# SCH_Imposter-Game_2026-03-29.net
KiCad netlist of a schematic drawn in EasyEDA
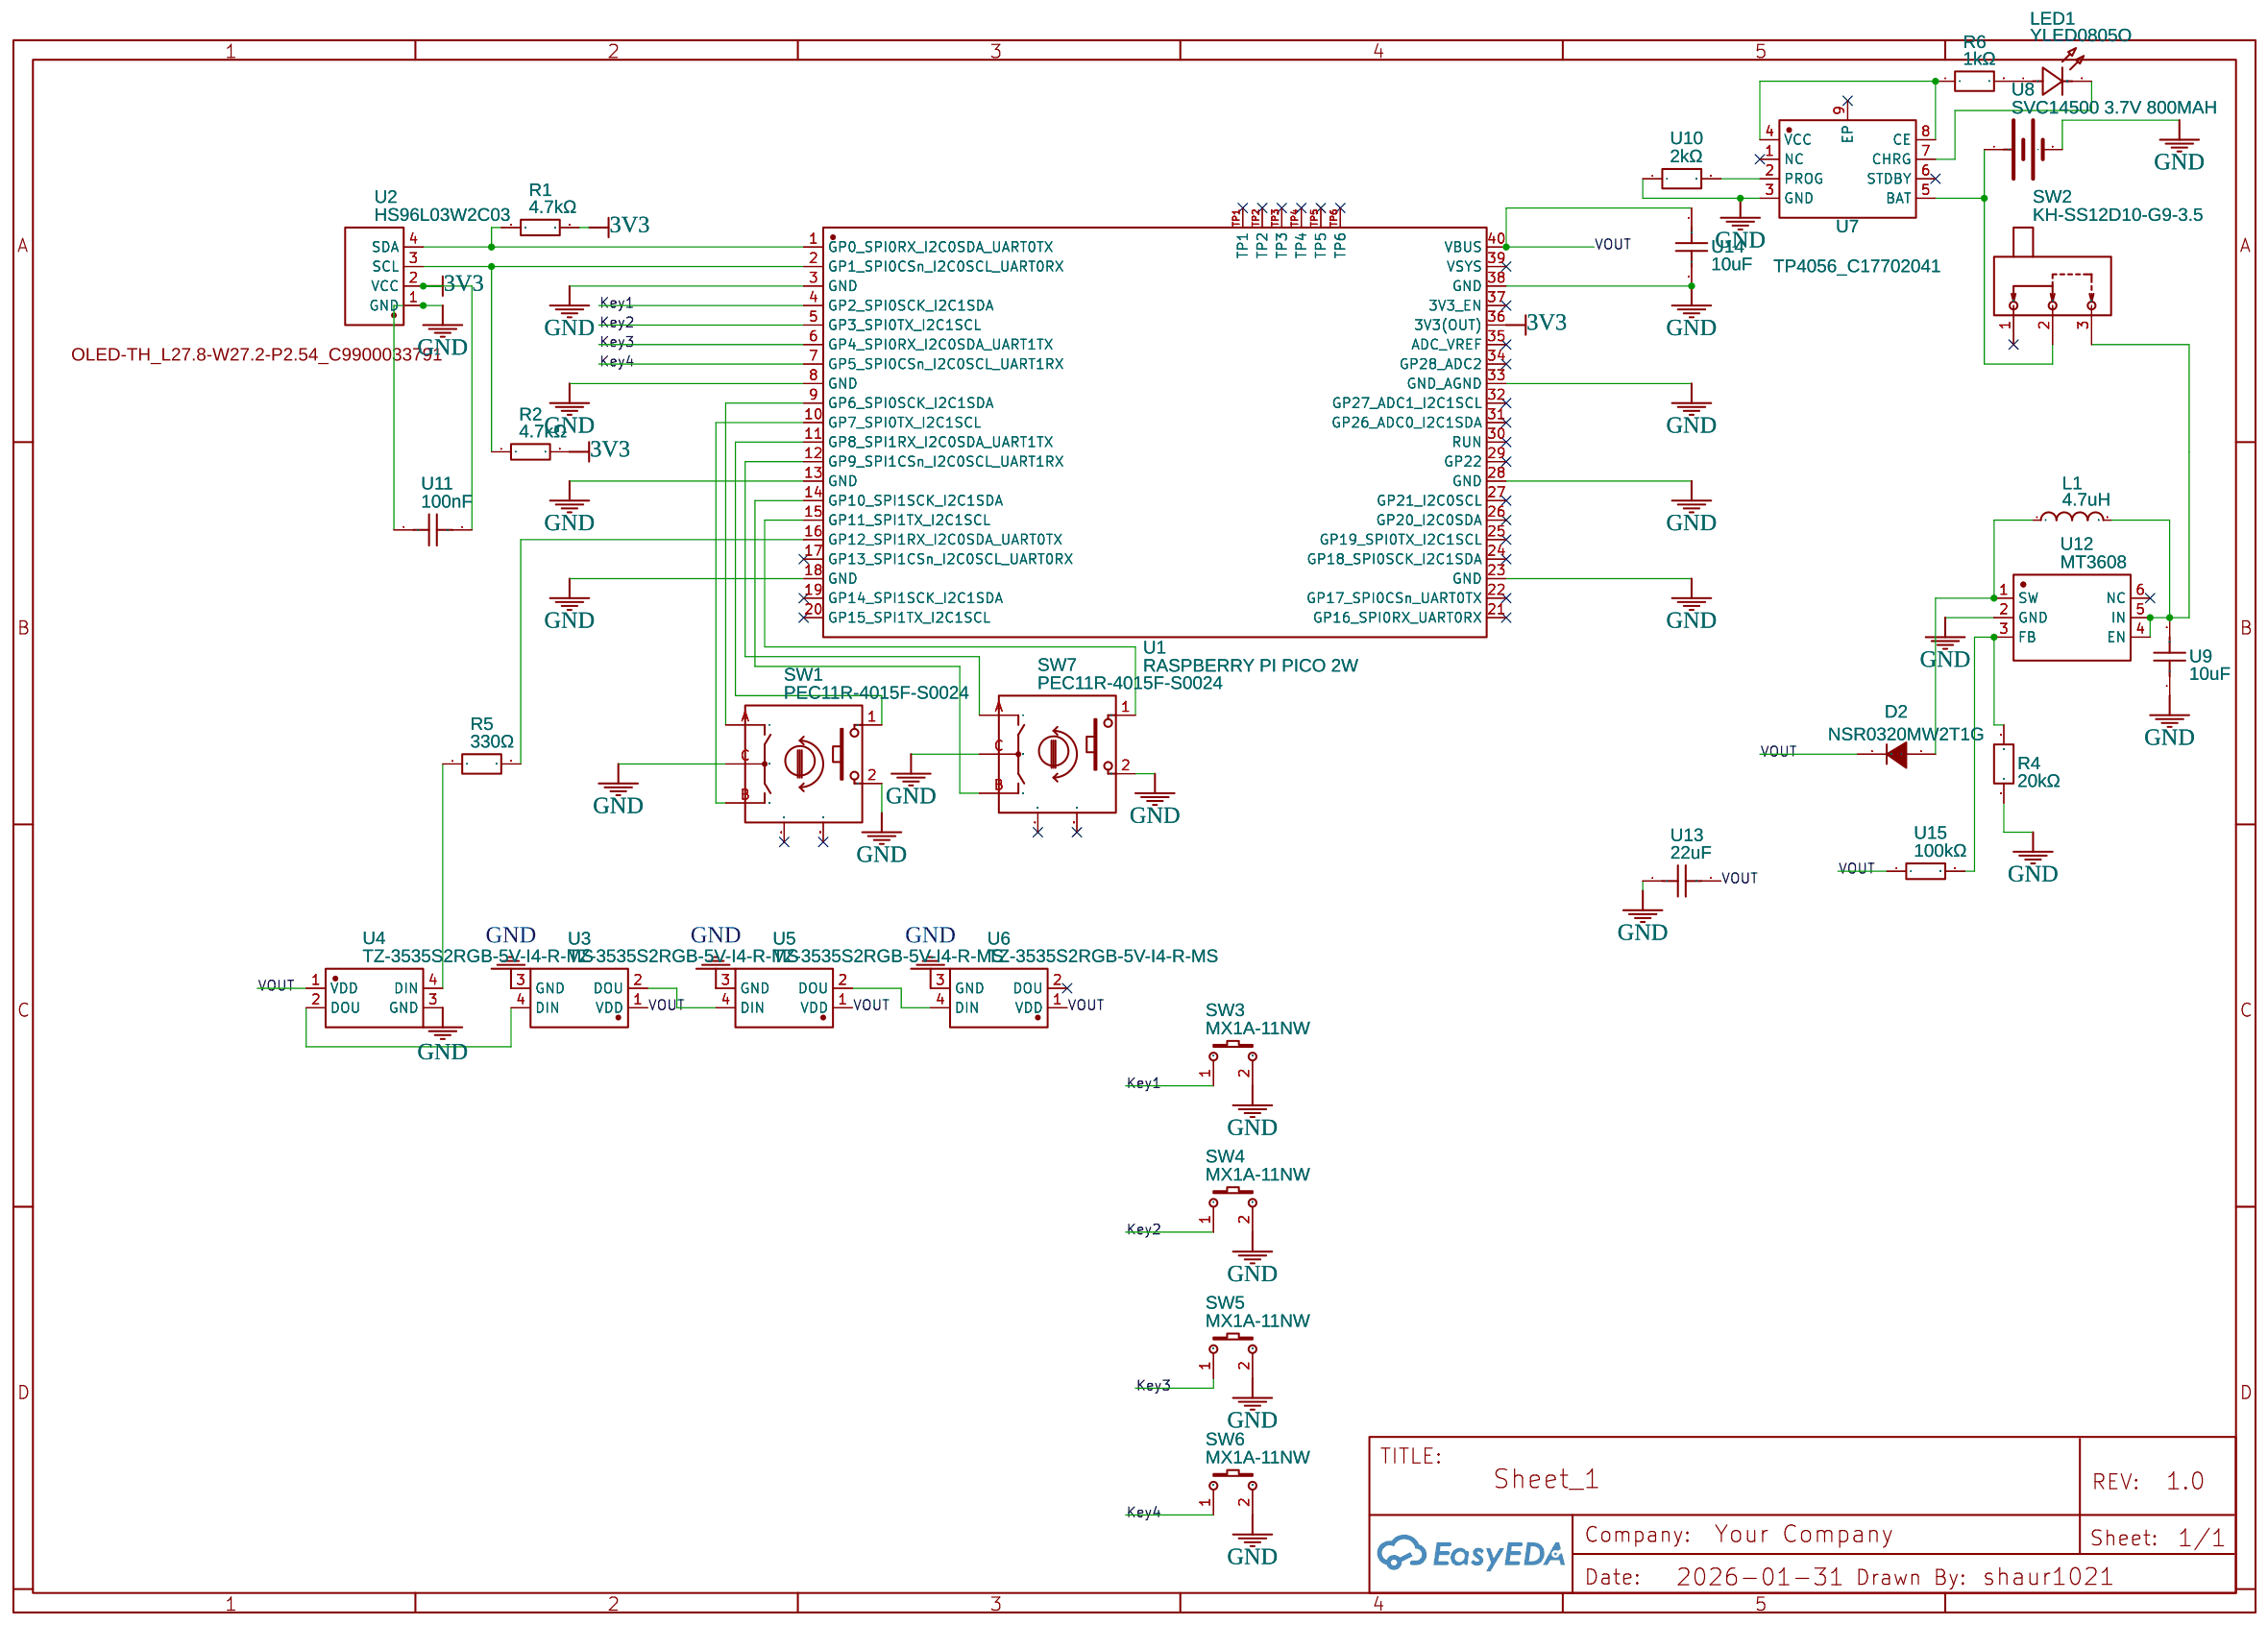
[diagram p0: schematic sheet]

(export (version "E")
  (design (tool "Eeschema 10.0.6"))
  (components
    (comp (ref "D2")
      (value "NSR0320MW2T1G")
      (fields (field (name "Manufacturer") "onsemi(安森美)"))
      (libsource (lib "") (part "NSR0320MW2T1G"))
    )
    (comp (ref "L1")
      (value "4.7uH")
      (fields (field (name "Manufacturer Part") "CD32N-4R7M") (field (name "Manufacturer") "MINGSTAR(登壹)"))
      (libsource (lib "") (part "CD32N-4R7M"))
    )
    (comp (ref "LED1")
      (value "YLED0805O")
      (fields (field (name "Manufacturer") "YONGYUTAI(永裕泰)"))
      (libsource (lib "") (part "YLED0805O"))
    )
    (comp (ref "R1")
      (value "4.7kΩ")
      (fields (field (name "Manufacturer Part") "CR254701F") (field (name "Manufacturer") "Meritek"))
      (libsource (lib "") (part "CR254701F"))
    )
    (comp (ref "R2")
      (value "4.7kΩ")
      (fields (field (name "Manufacturer Part") "CR254701F") (field (name "Manufacturer") "Meritek"))
      (libsource (lib "") (part "CR254701F"))
    )
    (comp (ref "R4")
      (value "20kΩ")
      (fields (field (name "Manufacturer Part") "FRC1206F2002TS") (field (name "Manufacturer") "FOJAN(富捷)"))
      (libsource (lib "") (part "FRC1206F2002TS"))
    )
    (comp (ref "R5")
      (value "330Ω")
      (fields
        (field (name "Manufacturer Part") "CRCW0805330RJNEA")
        (field (name "Manufacturer") "VISHAY(威世)")
      )
      (libsource (lib "") (part "CRCW0805330RJNEA"))
    )
    (comp (ref "R6")
      (value "1kΩ")
      (fields (field (name "Manufacturer Part") "APC0603B1K00N") (field (name "Manufacturer") "Ohmite"))
      (libsource (lib "") (part "APC0603B1K00N"))
    )
    (comp (ref "SW1")
      (value "PEC11R-4015F-S0024")
      (fields (field (name "Manufacturer") "BOURNS"))
      (libsource (lib "") (part "PEC11R-4015F-S0024"))
    )
    (comp (ref "SW2")
      (value "KH-SS12D10-G9-3.5")
      (fields (field (name "Manufacturer") "kinghelm(金航标)"))
      (libsource (lib "") (part "KH-SS12D10-G9-3.5"))
    )
    (comp (ref "SW3")
      (value "MX1A-11NW")
      (fields (field (name "Manufacturer") "CHERRY"))
      (libsource (lib "") (part "MX1A-11NW"))
    )
    (comp (ref "SW4")
      (value "MX1A-11NW")
      (fields (field (name "Manufacturer") "CHERRY"))
      (libsource (lib "") (part "MX1A-11NW"))
    )
    (comp (ref "SW5")
      (value "MX1A-11NW")
      (fields (field (name "Manufacturer") "CHERRY"))
      (libsource (lib "") (part "MX1A-11NW"))
    )
    (comp (ref "SW6")
      (value "MX1A-11NW")
      (fields (field (name "Manufacturer") "CHERRY"))
      (libsource (lib "") (part "MX1A-11NW"))
    )
    (comp (ref "SW7")
      (value "PEC11R-4015F-S0024")
      (fields (field (name "Manufacturer") "BOURNS"))
      (libsource (lib "") (part "PEC11R-4015F-S0024"))
    )
    (comp (ref "U1")
      (value "RASPBERRY PI PICO 2W")
      (fields
        (field (name "Manufacturer Part") "Raspberry Pi Pico 2W")
        (field (name "Manufacturer") "Raspberry Pi(树莓派)")
      )
      (libsource (lib "") (part "RASPBERRY PI PICO 2W"))
    )
    (comp (ref "U2")
      (value "HS96L03W2C03")
      (fields (field (name "Manufacturer") "HS(汉昇)"))
      (libsource (lib "") (part "HS96L03W2C03"))
    )
    (comp (ref "U3")
      (value "TZ-3535S2RGB-5V-I4-R-MS")
      (fields (field (name "Manufacturer") "TUOZHAN(拓展光电)"))
      (libsource (lib "") (part "TZ-3535S2RGB-5V-I4-R-MS_1"))
    )
    (comp (ref "U4")
      (value "TZ-3535S2RGB-5V-I4-R-MS")
      (fields (field (name "Manufacturer") "TUOZHAN(拓展光电)"))
      (libsource (lib "") (part "TZ-3535S2RGB-5V-I4-R-MS"))
    )
    (comp (ref "U5")
      (value "TZ-3535S2RGB-5V-I4-R-MS")
      (fields (field (name "Manufacturer") "TUOZHAN(拓展光电)"))
      (libsource (lib "") (part "TZ-3535S2RGB-5V-I4-R-MS_1"))
    )
    (comp (ref "U6")
      (value "TZ-3535S2RGB-5V-I4-R-MS")
      (fields (field (name "Manufacturer") "TUOZHAN(拓展光电)"))
      (libsource (lib "") (part "TZ-3535S2RGB-5V-I4-R-MS_1"))
    )
    (comp (ref "U7")
      (value "TP4056_C17702041")
      (fields (field (name "Manufacturer Part") "TP4056") (field (name "Manufacturer") "HXY MOSFET(华轩阳电子)"))
      (libsource (lib "") (part "TP4056_C17702041"))
    )
    (comp (ref "U8")
      (value "SVC14500 3.7V 800MAH")
      (fields
        (field (name "Manufacturer Part") "SVC14500 3.7V 800mAh")
        (field (name "Manufacturer") "Sharvin Power(经钛电子)")
      )
      (libsource (lib "") (part "SVC14500 3.7V 800MAH"))
    )
    (comp (ref "U9")
      (value "10uF")
      (fields (field (name "Manufacturer Part") "C4532X7R1C106M230KA") (field (name "Manufacturer") "TDK"))
      (libsource (lib "") (part "C4532X7R1C106M230KA_1"))
    )
    (comp (ref "U10")
      (value "2kΩ")
      (fields
        (field (name "Manufacturer Part") "TNPW04022K00BYEP")
        (field (name "Manufacturer") "VISHAY(威世)")
      )
      (libsource (lib "") (part "TNPW04022K00BYEP"))
    )
    (comp (ref "U11")
      (value "100nF")
      (fields (field (name "Manufacturer Part") "C1005X5R1A104K050BA") (field (name "Manufacturer") "TDK"))
      (libsource (lib "") (part "C1005X5R1A104K050BA"))
    )
    (comp (ref "U12")
      (value "MT3608")
      (fields (field (name "Manufacturer") "西安航天民芯"))
      (libsource (lib "") (part "MT3608"))
    )
    (comp (ref "U13")
      (value "22uF")
      (fields
        (field (name "Manufacturer Part") "MCAST32MSB7226KPNA01")
        (field (name "Manufacturer") "TAIYO YUDEN(太诱)")
      )
      (libsource (lib "") (part "MCAST32MSB7226KPNA01"))
    )
    (comp (ref "U14")
      (value "10uF")
      (fields (field (name "Manufacturer Part") "C4532X7R1C106M230KA") (field (name "Manufacturer") "TDK"))
      (libsource (lib "") (part "C4532X7R1C106M230KA"))
    )
    (comp (ref "U15")
      (value "100kΩ")
      (fields (field (name "Manufacturer Part") "CHR0805H-100KJ8") (field (name "Manufacturer") "Riedon"))
      (libsource (lib "") (part "CHR0805H-100KJ8"))
    )
  )
  (nets
    (net (code "1") (name "/Key1") (class "Default")
      (node (ref "SW3") (pin "1") (pinfunction "1_1") (pintype "unspecified"))
      (node (ref "U1") (pin "4") (pinfunction "GP2_SPI0SCK_I2C1SDA_4") (pintype "unspecified"))
    )
    (net (code "2") (name "/Key2") (class "Default")
      (node (ref "SW4") (pin "1") (pinfunction "1_1") (pintype "unspecified"))
      (node (ref "U1") (pin "5") (pinfunction "GP3_SPI0TX_I2C1SCL_5") (pintype "unspecified"))
    )
    (net (code "3") (name "/Key3") (class "Default")
      (node (ref "SW5") (pin "1") (pinfunction "1_1") (pintype "unspecified"))
      (node (ref "U1") (pin "6") (pinfunction "GP4_SPI0RX_I2C0SDA_UART1TX_6") (pintype "unspecified"))
    )
    (net (code "4") (name "/Key4") (class "Default")
      (node (ref "SW6") (pin "1") (pinfunction "1_1") (pintype "unspecified"))
      (node (ref "U1") (pin "7") (pinfunction "GP5_SPI0CSn_I2C0SCL_UART1RX_7") (pintype "unspecified"))
    )
    (net (code "5") (name "/VOUT") (class "Default")
      (node (ref "D2") (pin "1") (pinfunction "C_1") (pintype "unspecified"))
      (node (ref "U1") (pin "40") (pinfunction "VBUS_40") (pintype "unspecified"))
      (node (ref "U13") (pin "2") (pinfunction "2_2") (pintype "unspecified"))
      (node (ref "U14") (pin "1") (pinfunction "1_1") (pintype "unspecified"))
      (node (ref "U15") (pin "1") (pinfunction "1_1") (pintype "unspecified"))
      (node (ref "U3") (pin "1") (pinfunction "VDD_1") (pintype "unspecified"))
      (node (ref "U4") (pin "1") (pinfunction "VDD_1") (pintype "unspecified"))
      (node (ref "U5") (pin "1") (pinfunction "VDD_1") (pintype "unspecified"))
      (node (ref "U6") (pin "1") (pinfunction "VDD_1") (pintype "unspecified"))
    )
    (net (code "6") (name "3V3") (class "Default")
      (node (ref "R1") (pin "2") (pinfunction "2_2") (pintype "unspecified"))
      (node (ref "R2") (pin "2") (pinfunction "2_2") (pintype "unspecified"))
      (node (ref "U1") (pin "36") (pinfunction "3V3(OUT)_36") (pintype "unspecified"))
      (node (ref "U11") (pin "2") (pinfunction "2_2") (pintype "unspecified"))
      (node (ref "U2") (pin "2") (pinfunction "VCC_2") (pintype "unspecified"))
    )
    (net (code "7") (name "GND") (class "Default")
      (node (ref "R4") (pin "1") (pinfunction "1_1") (pintype "unspecified"))
      (node (ref "SW1") (pin "2") (pinfunction "2_2") (pintype "unspecified"))
      (node (ref "SW1") (pin "C") (pinfunction "C_C") (pintype "unspecified"))
      (node (ref "SW3") (pin "2") (pinfunction "2_2") (pintype "unspecified"))
      (node (ref "SW4") (pin "2") (pinfunction "2_2") (pintype "unspecified"))
      (node (ref "SW5") (pin "2") (pinfunction "2_2") (pintype "unspecified"))
      (node (ref "SW6") (pin "2") (pinfunction "2_2") (pintype "unspecified"))
      (node (ref "SW7") (pin "2") (pinfunction "2_2") (pintype "unspecified"))
      (node (ref "SW7") (pin "C") (pinfunction "C_C") (pintype "unspecified"))
      (node (ref "U1") (pin "13") (pinfunction "GND_13") (pintype "unspecified"))
      (node (ref "U1") (pin "18") (pinfunction "GND_18") (pintype "unspecified"))
      (node (ref "U1") (pin "23") (pinfunction "GND_23") (pintype "unspecified"))
      (node (ref "U1") (pin "28") (pinfunction "GND_28") (pintype "unspecified"))
      (node (ref "U1") (pin "3") (pinfunction "GND_3") (pintype "unspecified"))
      (node (ref "U1") (pin "33") (pinfunction "GND_AGND_33") (pintype "unspecified"))
      (node (ref "U1") (pin "38") (pinfunction "GND_38") (pintype "unspecified"))
      (node (ref "U1") (pin "8") (pinfunction "GND_8") (pintype "unspecified"))
      (node (ref "U10") (pin "1") (pinfunction "1_1") (pintype "unspecified"))
      (node (ref "U11") (pin "1") (pinfunction "1_1") (pintype "unspecified"))
      (node (ref "U12") (pin "2") (pinfunction "GND_2") (pintype "unspecified"))
      (node (ref "U13") (pin "1") (pinfunction "1_1") (pintype "unspecified"))
      (node (ref "U14") (pin "2") (pinfunction "2_2") (pintype "unspecified"))
      (node (ref "U2") (pin "1") (pinfunction "GND_1") (pintype "unspecified"))
      (node (ref "U3") (pin "3") (pinfunction "GND_3") (pintype "unspecified"))
      (node (ref "U4") (pin "3") (pinfunction "GND_3") (pintype "unspecified"))
      (node (ref "U5") (pin "3") (pinfunction "GND_3") (pintype "unspecified"))
      (node (ref "U6") (pin "3") (pinfunction "GND_3") (pintype "unspecified"))
      (node (ref "U7") (pin "3") (pinfunction "GND_3") (pintype "unspecified"))
      (node (ref "U8") (pin "2") (pinfunction "-_2") (pintype "passive"))
      (node (ref "U9") (pin "1") (pinfunction "1_1") (pintype "unspecified"))
    )
    (net (code "8") (name "Net-(D2-A)") (class "Default")
      (node (ref "D2") (pin "2") (pinfunction "A_2") (pintype "unspecified"))
      (node (ref "L1") (pin "1") (pinfunction "1_1") (pintype "unspecified"))
      (node (ref "U12") (pin "1") (pinfunction "SW_1") (pintype "unspecified"))
    )
    (net (code "9") (name "Net-(LED1-A)") (class "Default")
      (node (ref "LED1") (pin "1") (pinfunction "A_1") (pintype "unspecified"))
      (node (ref "R6") (pin "2") (pinfunction "2_2") (pintype "unspecified"))
    )
    (net (code "10") (name "Net-(LED1-C)") (class "Default")
      (node (ref "LED1") (pin "2") (pinfunction "C_2") (pintype "unspecified"))
      (node (ref "U7") (pin "7") (pinfunction "CHRG_7") (pintype "unspecified"))
    )
    (net (code "11") (name "Net-(U1-GP0_SPI0RX_I2C0SDA_UART0TX)") (class "Default")
      (node (ref "R1") (pin "1") (pinfunction "1_1") (pintype "unspecified"))
      (node (ref "U1") (pin "1") (pinfunction "GP0_SPI0RX_I2C0SDA_UART0TX_1") (pintype "unspecified"))
      (node (ref "U2") (pin "4") (pinfunction "SDA_4") (pintype "unspecified"))
    )
    (net (code "12") (name "Net-(U1-GP1_SPI0CSn_I2C0SCL_UART0RX)") (class "Default")
      (node (ref "R2") (pin "1") (pinfunction "1_1") (pintype "unspecified"))
      (node (ref "U1") (pin "2") (pinfunction "GP1_SPI0CSn_I2C0SCL_UART0RX_2") (pintype "unspecified"))
      (node (ref "U2") (pin "3") (pinfunction "SCL_3") (pintype "unspecified"))
    )
    (net (code "13") (name "Net-(U1-GP6_SPI0SCK_I2C1SDA)") (class "Default")
      (node (ref "SW1") (pin "A") (pinfunction "A_A") (pintype "unspecified"))
      (node (ref "U1") (pin "9") (pinfunction "GP6_SPI0SCK_I2C1SDA_9") (pintype "unspecified"))
    )
    (net (code "14") (name "Net-(U1-GP7_SPI0TX_I2C1SCL)") (class "Default")
      (node (ref "SW1") (pin "B") (pinfunction "B_B") (pintype "unspecified"))
      (node (ref "U1") (pin "10") (pinfunction "GP7_SPI0TX_I2C1SCL_10") (pintype "unspecified"))
    )
    (net (code "15") (name "Net-(U1-GP8_SPI1RX_I2C0SDA_UART1TX)") (class "Default")
      (node (ref "SW1") (pin "1") (pinfunction "1_1") (pintype "unspecified"))
      (node (ref "U1") (pin "11") (pinfunction "GP8_SPI1RX_I2C0SDA_UART1TX_11") (pintype "unspecified"))
    )
    (net (code "16") (name "Net-(U1-GP9_SPI1CSn_I2C0SCL_UART1RX)") (class "Default")
      (node (ref "SW7") (pin "A") (pinfunction "A_A") (pintype "unspecified"))
      (node (ref "U1") (pin "12") (pinfunction "GP9_SPI1CSn_I2C0SCL_UART1RX_12") (pintype "unspecified"))
    )
    (net (code "17") (name "Net-(U1-GP10_SPI1SCK_I2C1SDA)") (class "Default")
      (node (ref "SW7") (pin "B") (pinfunction "B_B") (pintype "unspecified"))
      (node (ref "U1") (pin "14") (pinfunction "GP10_SPI1SCK_I2C1SDA_14") (pintype "unspecified"))
    )
    (net (code "18") (name "Net-(U1-GP11_SPI1TX_I2C1SCL)") (class "Default")
      (node (ref "SW7") (pin "1") (pinfunction "1_1") (pintype "unspecified"))
      (node (ref "U1") (pin "15") (pinfunction "GP11_SPI1TX_I2C1SCL_15") (pintype "unspecified"))
    )
    (net (code "19") (name "Net-(U1-GP12_SPI1RX_I2C0SDA_UART0TX)") (class "Default")
      (node (ref "R5") (pin "2") (pinfunction "2_2") (pintype "unspecified"))
      (node (ref "U1") (pin "16") (pinfunction "GP12_SPI1RX_I2C0SDA_UART0TX_16") (pintype "unspecified"))
    )
    (net (code "20") (name "Net-(U3-DIN)") (class "Default")
      (node (ref "U3") (pin "4") (pinfunction "DIN_4") (pintype "unspecified"))
      (node (ref "U4") (pin "2") (pinfunction "DOU_2") (pintype "unspecified"))
    )
    (net (code "21") (name "Net-(U3-DOU)") (class "Default")
      (node (ref "U3") (pin "2") (pinfunction "DOU_2") (pintype "unspecified"))
      (node (ref "U5") (pin "4") (pinfunction "DIN_4") (pintype "unspecified"))
    )
    (net (code "22") (name "Net-(U4-DIN)") (class "Default")
      (node (ref "R5") (pin "1") (pinfunction "1_1") (pintype "unspecified"))
      (node (ref "U4") (pin "4") (pinfunction "DIN_4") (pintype "unspecified"))
    )
    (net (code "23") (name "Net-(U5-DOU)") (class "Default")
      (node (ref "U5") (pin "2") (pinfunction "DOU_2") (pintype "unspecified"))
      (node (ref "U6") (pin "4") (pinfunction "DIN_4") (pintype "unspecified"))
    )
    (net (code "24") (name "Net-(U7-BAT)") (class "Default")
      (node (ref "SW2") (pin "2") (pinfunction "2_2") (pintype "unspecified"))
      (node (ref "U7") (pin "5") (pinfunction "BAT_5") (pintype "unspecified"))
      (node (ref "U8") (pin "1") (pinfunction "+_1") (pintype "passive"))
    )
    (net (code "25") (name "Net-(U7-CE)") (class "Default")
      (node (ref "R6") (pin "1") (pinfunction "1_1") (pintype "unspecified"))
      (node (ref "U7") (pin "4") (pinfunction "VCC_4") (pintype "unspecified"))
      (node (ref "U7") (pin "8") (pinfunction "CE_8") (pintype "unspecified"))
    )
    (net (code "26") (name "Net-(U7-PROG)") (class "Default")
      (node (ref "U10") (pin "2") (pinfunction "2_2") (pintype "unspecified"))
      (node (ref "U7") (pin "2") (pinfunction "PROG_2") (pintype "unspecified"))
    )
    (net (code "27") (name "Net-(U12-EN)") (class "Default")
      (node (ref "L1") (pin "2") (pinfunction "2_2") (pintype "unspecified"))
      (node (ref "SW2") (pin "3") (pinfunction "3_3") (pintype "unspecified"))
      (node (ref "U12") (pin "4") (pinfunction "EN_4") (pintype "unspecified"))
      (node (ref "U12") (pin "5") (pinfunction "IN_5") (pintype "unspecified"))
      (node (ref "U9") (pin "2") (pinfunction "2_2") (pintype "unspecified"))
    )
    (net (code "28") (name "Net-(U12-FB)") (class "Default")
      (node (ref "R4") (pin "2") (pinfunction "2_2") (pintype "unspecified"))
      (node (ref "U12") (pin "3") (pinfunction "FB_3") (pintype "unspecified"))
      (node (ref "U15") (pin "2") (pinfunction "2_2") (pintype "unspecified"))
    )
    (net (code "29") (name "unconnected-(SW1-PadMT1)") (class "Default")
      (node (ref "SW1") (pin "MT1") (pinfunction "MT1_MT1") (pintype "unspecified+no_connect"))
    )
    (net (code "30") (name "unconnected-(SW1-PadMT2)") (class "Default")
      (node (ref "SW1") (pin "MT2") (pinfunction "MT2_MT2") (pintype "unspecified+no_connect"))
    )
    (net (code "31") (name "unconnected-(SW2-Pad1)") (class "Default")
      (node (ref "SW2") (pin "1") (pinfunction "1_1") (pintype "unspecified+no_connect"))
    )
    (net (code "32") (name "unconnected-(SW7-PadMT1)") (class "Default")
      (node (ref "SW7") (pin "MT1") (pinfunction "MT1_MT1") (pintype "unspecified+no_connect"))
    )
    (net (code "33") (name "unconnected-(SW7-PadMT2)") (class "Default")
      (node (ref "SW7") (pin "MT2") (pinfunction "MT2_MT2") (pintype "unspecified+no_connect"))
    )
    (net (code "34") (name "unconnected-(U1-3V3_EN-Pad37)") (class "Default")
      (node (ref "U1") (pin "37") (pinfunction "3V3_EN_37") (pintype "unspecified+no_connect"))
    )
    (net (code "35") (name "unconnected-(U1-ADC_VREF-Pad35)") (class "Default")
      (node (ref "U1") (pin "35") (pinfunction "ADC_VREF_35") (pintype "unspecified+no_connect"))
    )
    (net (code "36") (name "unconnected-(U1-GP13_SPI1CSn_I2C0SCL_UART0RX-Pad17)") (class "Default")
      (node (ref "U1") (pin "17") (pinfunction "GP13_SPI1CSn_I2C0SCL_UART0RX_17") (pintype "unspecified+no_connect"))
    )
    (net (code "37") (name "unconnected-(U1-GP14_SPI1SCK_I2C1SDA-Pad19)") (class "Default")
      (node (ref "U1") (pin "19") (pinfunction "GP14_SPI1SCK_I2C1SDA_19") (pintype "unspecified+no_connect"))
    )
    (net (code "38") (name "unconnected-(U1-GP15_SPI1TX_I2C1SCL-Pad20)") (class "Default")
      (node (ref "U1") (pin "20") (pinfunction "GP15_SPI1TX_I2C1SCL_20") (pintype "unspecified+no_connect"))
    )
    (net (code "39") (name "unconnected-(U1-GP16_SPI0RX_UART0RX-Pad21)") (class "Default")
      (node (ref "U1") (pin "21") (pinfunction "GP16_SPI0RX_UART0RX_21") (pintype "unspecified+no_connect"))
    )
    (net (code "40") (name "unconnected-(U1-GP17_SPI0CSn_UART0TX-Pad22)") (class "Default")
      (node (ref "U1") (pin "22") (pinfunction "GP17_SPI0CSn_UART0TX_22") (pintype "unspecified+no_connect"))
    )
    (net (code "41") (name "unconnected-(U1-GP18_SPI0SCK_I2C1SDA-Pad24)") (class "Default")
      (node (ref "U1") (pin "24") (pinfunction "GP18_SPI0SCK_I2C1SDA_24") (pintype "unspecified+no_connect"))
    )
    (net (code "42") (name "unconnected-(U1-GP19_SPI0TX_I2C1SCL-Pad25)") (class "Default")
      (node (ref "U1") (pin "25") (pinfunction "GP19_SPI0TX_I2C1SCL_25") (pintype "unspecified+no_connect"))
    )
    (net (code "43") (name "unconnected-(U1-GP20_I2C0SDA-Pad26)") (class "Default")
      (node (ref "U1") (pin "26") (pinfunction "GP20_I2C0SDA_26") (pintype "unspecified+no_connect"))
    )
    (net (code "44") (name "unconnected-(U1-GP21_I2C0SCL-Pad27)") (class "Default")
      (node (ref "U1") (pin "27") (pinfunction "GP21_I2C0SCL_27") (pintype "unspecified+no_connect"))
    )
    (net (code "45") (name "unconnected-(U1-GP22-Pad29)") (class "Default")
      (node (ref "U1") (pin "29") (pinfunction "GP22_29") (pintype "unspecified+no_connect"))
    )
    (net (code "46") (name "unconnected-(U1-GP26_ADC0_I2C1SDA-Pad31)") (class "Default")
      (node (ref "U1") (pin "31") (pinfunction "GP26_ADC0_I2C1SDA_31") (pintype "unspecified+no_connect"))
    )
    (net (code "47") (name "unconnected-(U1-GP27_ADC1_I2C1SCL-Pad32)") (class "Default")
      (node (ref "U1") (pin "32") (pinfunction "GP27_ADC1_I2C1SCL_32") (pintype "unspecified+no_connect"))
    )
    (net (code "48") (name "unconnected-(U1-GP28_ADC2-Pad34)") (class "Default")
      (node (ref "U1") (pin "34") (pinfunction "GP28_ADC2_34") (pintype "unspecified+no_connect"))
    )
    (net (code "49") (name "unconnected-(U1-PadTP1)") (class "Default")
      (node (ref "U1") (pin "TP1") (pinfunction "TP1_TP1") (pintype "unspecified+no_connect"))
    )
    (net (code "50") (name "unconnected-(U1-PadTP2)") (class "Default")
      (node (ref "U1") (pin "TP2") (pinfunction "TP2_TP2") (pintype "unspecified+no_connect"))
    )
    (net (code "51") (name "unconnected-(U1-PadTP3)") (class "Default")
      (node (ref "U1") (pin "TP3") (pinfunction "TP3_TP3") (pintype "unspecified+no_connect"))
    )
    (net (code "52") (name "unconnected-(U1-PadTP4)") (class "Default")
      (node (ref "U1") (pin "TP4") (pinfunction "TP4_TP4") (pintype "unspecified+no_connect"))
    )
    (net (code "53") (name "unconnected-(U1-PadTP5)") (class "Default")
      (node (ref "U1") (pin "TP5") (pinfunction "TP5_TP5") (pintype "unspecified+no_connect"))
    )
    (net (code "54") (name "unconnected-(U1-PadTP6)") (class "Default")
      (node (ref "U1") (pin "TP6") (pinfunction "TP6_TP6") (pintype "unspecified+no_connect"))
    )
    (net (code "55") (name "unconnected-(U1-RUN-Pad30)") (class "Default")
      (node (ref "U1") (pin "30") (pinfunction "RUN_30") (pintype "unspecified+no_connect"))
    )
    (net (code "56") (name "unconnected-(U1-VSYS-Pad39)") (class "Default")
      (node (ref "U1") (pin "39") (pinfunction "VSYS_39") (pintype "unspecified+no_connect"))
    )
    (net (code "57") (name "unconnected-(U6-DOU-Pad2)") (class "Default")
      (node (ref "U6") (pin "2") (pinfunction "DOU_2") (pintype "unspecified+no_connect"))
    )
    (net (code "58") (name "unconnected-(U7-EP-Pad9)") (class "Default")
      (node (ref "U7") (pin "9") (pinfunction "EP_9") (pintype "unspecified+no_connect"))
    )
    (net (code "59") (name "unconnected-(U7-NC-Pad1)") (class "Default")
      (node (ref "U7") (pin "1") (pinfunction "NC_1") (pintype "unspecified+no_connect"))
    )
    (net (code "60") (name "unconnected-(U7-STDBY-Pad6)") (class "Default")
      (node (ref "U7") (pin "6") (pinfunction "STDBY_6") (pintype "unspecified+no_connect"))
    )
    (net (code "61") (name "unconnected-(U12-NC-Pad6)") (class "Default")
      (node (ref "U12") (pin "6") (pinfunction "NC_6") (pintype "unspecified+no_connect"))
    )
  )
)
